# PAC1932_Breakout.net
KiCad netlist of a schematic drawn in EAGLE
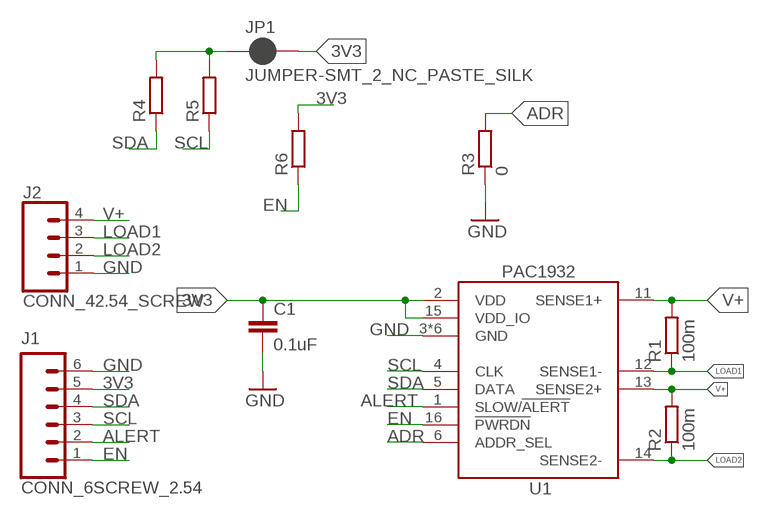
[diagram p0: schematic, sheet 1]

(export (version "E")
  (design (tool "Eeschema 10.0.6"))
  (components
    (comp (ref "C1")
      (value "0.1uF")
      (footprint "eagle-import:C0402")
      (fields (field (name "MF") "Murata") (field (name "MPN") "GCM155R71C104KA55D"))
      (libsource (lib "eagle-import") (part "C-EUC04020.1UF"))
    )
    (comp (ref "J1")
      (value "CONN_6SCREW_2.54")
      (footprint "eagle-import:1X06_SCREW")
      (fields (field (name "MF") "OnShore") (field (name "MPN") "OSTVN06A150"))
      (libsource (lib "eagle-import") (part "CONN_6SCREW_2.54"))
    )
    (comp (ref "J2")
      (value "CONN_42.54_SCREW")
      (footprint "eagle-import:1X04_SCREW")
      (fields (field (name "MF") "On Shore") (field (name "MPN") "OSTVN04A150"))
      (libsource (lib "eagle-import") (part "CONN_42.54_SCREW"))
    )
    (comp (ref "JP1")
      (value "JUMPER-SMT_2_NC_PASTE_SILK")
      (footprint "eagle-import:SMT-JUMPER_2_NC_PASTE_SILK")
      (libsource (lib "eagle-import") (part "JUMPER-SMT_2_NC_PASTE_SILK"))
    )
    (comp (ref "R1")
      (value "100m")
      (footprint "eagle-import:R0805")
      (fields (field (name "MF") "Panasonic") (field (name "MPN") "ERJ-6DSFR10V"))
      (libsource (lib "eagle-import") (part "R-EU_R08050.1"))
    )
    (comp (ref "R2")
      (value "100m")
      (footprint "eagle-import:R0805")
      (fields (field (name "MF") "Panasonic") (field (name "MPN") "ERJ-6DSFR10V"))
      (libsource (lib "eagle-import") (part "R-EU_R08050.1"))
    )
    (comp (ref "R3")
      (value "0")
      (footprint "eagle-import:R0402")
      (fields (field (name "MF") "Yageo") (field (name "MPN") "RC0402JR-070RL"))
      (libsource (lib "eagle-import") (part "R-EU_R04020.0"))
    )
    (comp (ref "R4")
      (value "R-EU_10KR0402")
      (footprint "eagle-import:R0402")
      (fields
        (field (name "MF") "Yageo")
        (field (name "MPN") "RC0402FR-0710KL")
        (field (name "VALUE_PART") "10k")
      )
      (libsource (lib "eagle-import") (part "R-EU_R040210K"))
    )
    (comp (ref "R5")
      (value "R-EU_10KR0402")
      (footprint "eagle-import:R0402")
      (fields
        (field (name "MF") "Yageo")
        (field (name "MPN") "RC0402FR-0710KL")
        (field (name "VALUE_PART") "10k")
      )
      (libsource (lib "eagle-import") (part "R-EU_R040210K"))
    )
    (comp (ref "R6")
      (value "R-EU_10KR0402")
      (footprint "eagle-import:R0402")
      (fields
        (field (name "MF") "Yageo")
        (field (name "MPN") "RC0402FR-0710KL")
        (field (name "VALUE_PART") "10k")
      )
      (libsource (lib "eagle-import") (part "R-EU_R040210K"))
    )
    (comp (ref "U1")
      (value "PAC1932QFN")
      (footprint "eagle-import:QFN16")
      (fields (field (name "MF") "Microchip") (field (name "MPN") "PAC1932T-I/JQ"))
      (libsource (lib "eagle-import") (part "PAC1932QFN"))
    )
  )
  (nets
    (net (code "1") (name "/ALERT") (class "Default")
      (node (ref "J1") (pin "2") (pinfunction "2_2") (pintype "passive"))
      (node (ref "U1") (pin "1") (pinfunction "SLOW/~{ALERT}_1") (pintype "bidirectional"))
    )
    (net (code "2") (name "/EN") (class "Default")
      (node (ref "J1") (pin "1") (pinfunction "1_1") (pintype "passive"))
      (node (ref "R6") (pin "1") (pinfunction "1_1") (pintype "passive"))
      (node (ref "U1") (pin "16") (pinfunction "~{PWRDN}_16") (pintype "input"))
    )
    (net (code "3") (name "/SCL") (class "Default")
      (node (ref "J1") (pin "3") (pinfunction "3_3") (pintype "passive"))
      (node (ref "R5") (pin "1") (pinfunction "1_1") (pintype "passive"))
      (node (ref "U1") (pin "4") (pinfunction "CLK_4") (pintype "input"))
    )
    (net (code "4") (name "/SDA") (class "Default")
      (node (ref "J1") (pin "4") (pinfunction "4_4") (pintype "passive"))
      (node (ref "R4") (pin "1") (pinfunction "1_1") (pintype "passive"))
      (node (ref "U1") (pin "5") (pinfunction "DATA_5") (pintype "bidirectional"))
    )
    (net (code "5") (name "3V3") (class "Default")
      (node (ref "C1") (pin "1") (pinfunction "1_1") (pintype "passive"))
      (node (ref "J1") (pin "5") (pinfunction "5_5") (pintype "passive"))
      (node (ref "JP1") (pin "2") (pinfunction "2_2") (pintype "passive"))
      (node (ref "R6") (pin "2") (pinfunction "2_2") (pintype "passive"))
      (node (ref "U1") (pin "15") (pinfunction "VDD_IO_15") (pintype "open_collector"))
      (node (ref "U1") (pin "2") (pinfunction "VDD_2") (pintype "power_in"))
    )
    (net (code "6") (name "ADR") (class "Default")
      (node (ref "R3") (pin "2") (pinfunction "2_2") (pintype "passive"))
      (node (ref "U1") (pin "6") (pinfunction "ADDR_SEL_6") (pintype "input"))
    )
    (net (code "7") (name "GND") (class "Default")
      (node (ref "C1") (pin "2") (pinfunction "2_2") (pintype "passive"))
      (node (ref "J1") (pin "6") (pinfunction "6_6") (pintype "passive"))
      (node (ref "J2") (pin "1") (pinfunction "1_1") (pintype "passive"))
      (node (ref "R3") (pin "1") (pinfunction "1_1") (pintype "passive"))
      (node (ref "U1") (pin "10") (pinfunction "GND_10") (pintype "power_in"))
      (node (ref "U1") (pin "3") (pinfunction "GND_3") (pintype "power_in"))
      (node (ref "U1") (pin "7") (pinfunction "GND_7") (pintype "power_in"))
      (node (ref "U1") (pin "8") (pinfunction "GND_8") (pintype "power_in"))
      (node (ref "U1") (pin "9") (pinfunction "GND_9") (pintype "power_in"))
      (node (ref "U1") (pin "EP") (pinfunction "GND_EP") (pintype "power_in"))
    )
    (net (code "8") (name "LOAD1") (class "Default")
      (node (ref "J2") (pin "3") (pinfunction "3_3") (pintype "passive"))
      (node (ref "R1") (pin "1") (pinfunction "1_1") (pintype "passive"))
      (node (ref "U1") (pin "12") (pinfunction "SENSE1-_12") (pintype "input"))
    )
    (net (code "9") (name "LOAD2") (class "Default")
      (node (ref "J2") (pin "2") (pinfunction "2_2") (pintype "passive"))
      (node (ref "R2") (pin "1") (pinfunction "1_1") (pintype "passive"))
      (node (ref "U1") (pin "14") (pinfunction "SENSE2-_14") (pintype "input"))
    )
    (net (code "10") (name "Net-(JP1-Pad1)") (class "Default")
      (node (ref "JP1") (pin "1") (pinfunction "1_1") (pintype "passive"))
      (node (ref "R4") (pin "2") (pinfunction "2_2") (pintype "passive"))
      (node (ref "R5") (pin "2") (pinfunction "2_2") (pintype "passive"))
    )
    (net (code "11") (name "V+") (class "Default")
      (node (ref "J2") (pin "4") (pinfunction "4_4") (pintype "passive"))
      (node (ref "R1") (pin "2") (pinfunction "2_2") (pintype "passive"))
      (node (ref "R2") (pin "2") (pinfunction "2_2") (pintype "passive"))
      (node (ref "U1") (pin "11") (pinfunction "SENSE1+_11") (pintype "input"))
      (node (ref "U1") (pin "13") (pinfunction "SENSE2+_13") (pintype "input"))
    )
  )
)
